# Sheet2.net
KiCad netlist of a schematic drawn in Altium Designer
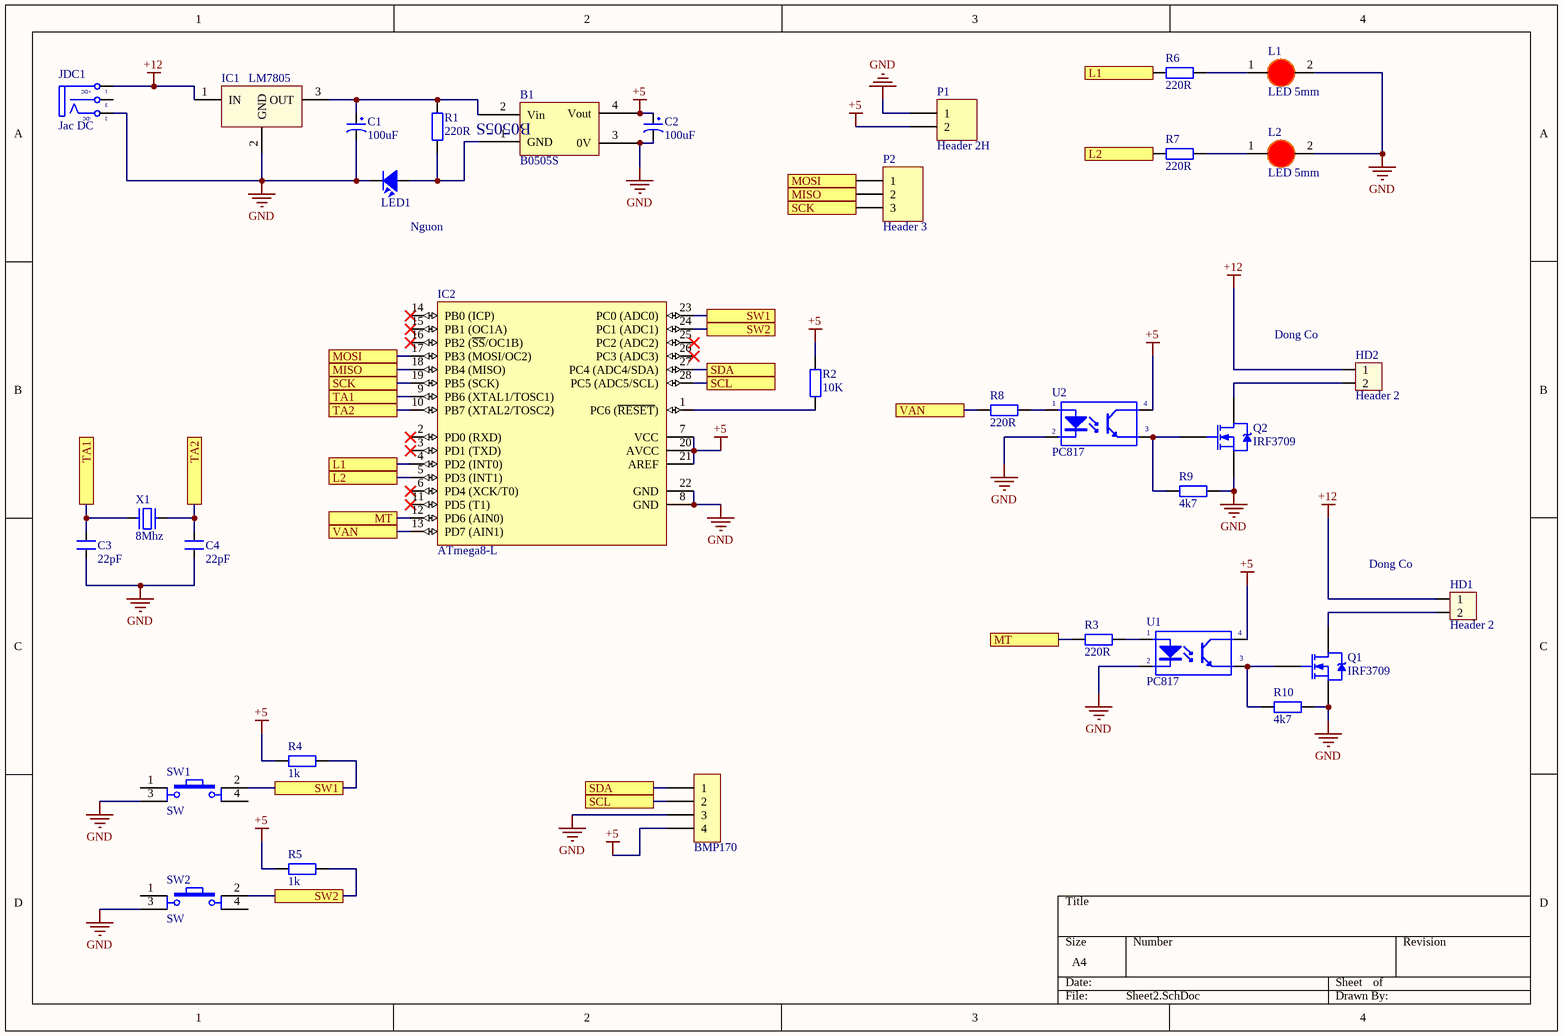
[diagram p0: Sheet2.SchDoc]

(export (version "E")
  (design (tool "Eeschema 10.0.6"))
  (components
    (comp (ref "B1")
      (value "B0505S")
      (footprint "B0505S")
      (description "Cắm")
      (libsource (lib "Altium_Lib_by_KhueNguyenCreator") (part "B0505S"))
    )
    (comp (ref "C1")
      (value "100uF")
      (footprint "tu hoa 8mm")
      (description "Cắm")
      (libsource (lib "Altium_Lib_by_KhueNguyenCreator") (part "Tu Hoa 100uF 35V 8x11"))
    )
    (comp (ref "C2")
      (value "100uF")
      (footprint "tu hoa 8mm")
      (description "Cắm")
      (libsource (lib "Altium_Lib_by_KhueNguyenCreator") (part "Tu Hoa 100uF 35V 8x11"))
    )
    (comp (ref "C3")
      (value "22pF")
      (footprint "CN1")
      (description "Cap np  1pF - 472pF")
      (libsource (lib "syhaunguyen") (part "CN1"))
    )
    (comp (ref "C4")
      (value "22pF")
      (footprint "CN1")
      (description "Cap np  1pF - 472pF")
      (libsource (lib "syhaunguyen") (part "CN1"))
    )
    (comp (ref "H1")
      (value "BMP170")
      (footprint "XH2.54M-4")
      (description "Cắm")
      (libsource (lib "Altium_Lib_by_KhueNguyenCreator") (part "Header 4P 2.54 Duc Thang"))
    )
    (comp (ref "HD1")
      (value "Header 2")
      (footprint "HED2")
      (description "Header 2 (Green)")
      (libsource (lib "syhaunguyen") (part "Hed2"))
    )
    (comp (ref "HD2")
      (value "Header 2")
      (footprint "HED2")
      (description "Header 2 (Green)")
      (libsource (lib "syhaunguyen") (part "Hed2"))
    )
    (comp (ref "IC1")
      (value "LM7805")
      (footprint "QTO-220")
      (description "On ap +, from + 5 to + 24VDC")
      (libsource (lib "syhaunguyen") (part "LM78xx"))
    )
    (comp (ref "IC2")
      (value "ATmega8-L")
      (footprint "DIP28/W0.3")
      (description "8-Bit AVR Microcontroller with 8K Bytes of In-System Programmable Flash Memory")
      (libsource (lib "syhaunguyen") (part "ATmega8-L"))
    )
    (comp (ref "JDC1")
      (value "Jac DC")
      (footprint "DC-IN")
      (description "Jac DC input")
      (libsource (lib "syhaunguyen") (part "DCIN"))
    )
    (comp (ref "L1")
      (value "LED 5mm")
      (footprint "LED-5MM-RED")
      (description "Cắm")
      (libsource (lib "Altium_Lib_by_KhueNguyenCreator") (part "LED 5mm Do"))
    )
    (comp (ref "L2")
      (value "LED 5mm")
      (footprint "LED-5MM-RED")
      (description "Cắm")
      (libsource (lib "Altium_Lib_by_KhueNguyenCreator") (part "LED 5mm Do"))
    )
    (comp (ref "LED1")
      (value "LED")
      (footprint "LED-3")
      (description "LED Single colour Green and Red")
      (libsource (lib "syhaunguyen") (part "LED"))
    )
    (comp (ref "P1")
      (value "Header 2H")
      (footprint "HDR1X2H")
      (description "Header, 2-Pin, Right Angle")
      (fields (field (name "PUBLISHER") "Altium Limited"))
      (libsource (lib "Cty1") (part "Header 2H"))
    )
    (comp (ref "P2")
      (value "Header 3")
      (footprint "HDR1X3")
      (description "Header, 3-Pin")
      (fields (field (name "PUBLISHER") "Altium Limited"))
      (libsource (lib "Cty1") (part "Header 3"))
    )
    (comp (ref "Q1")
      (value "IRF3709")
      (footprint "TO220")
      (description "N-Channel Power MOSFET")
      (libsource (lib "Altium_Lib_by_KhueNguyenCreator") (part "IRF3709 DIP"))
    )
    (comp (ref "Q2")
      (value "IRF3709")
      (footprint "TO220")
      (description "N-Channel Power MOSFET")
      (libsource (lib "Altium_Lib_by_KhueNguyenCreator") (part "IRF3709 DIP"))
    )
    (comp (ref "R1")
      (value "220R")
      (footprint "R1/4W")
      (description "Resistor 1/4W")
      (libsource (lib "syhaunguyen") (part "R1/4W"))
    )
    (comp (ref "R2")
      (value "10K")
      (footprint "R1/4W")
      (description "Resistor 1/4W")
      (libsource (lib "syhaunguyen") (part "R1/4W"))
    )
    (comp (ref "R3")
      (value "220R")
      (footprint "R1/4W")
      (description "Resistor 1/4W")
      (libsource (lib "syhaunguyen") (part "R1/4W"))
    )
    (comp (ref "R4")
      (value "1k")
      (footprint "R1/4W")
      (description "Resistor 1/4W")
      (libsource (lib "syhaunguyen") (part "R1/4W"))
    )
    (comp (ref "R5")
      (value "1k")
      (footprint "R1/4W")
      (description "Resistor 1/4W")
      (libsource (lib "syhaunguyen") (part "R1/4W"))
    )
    (comp (ref "R6")
      (value "220R")
      (footprint "R1/4W")
      (description "Resistor 1/4W")
      (libsource (lib "syhaunguyen") (part "R1/4W"))
    )
    (comp (ref "R7")
      (value "220R")
      (footprint "R1/4W")
      (description "Resistor 1/4W")
      (libsource (lib "syhaunguyen") (part "R1/4W"))
    )
    (comp (ref "R8")
      (value "220R")
      (footprint "R1/4W")
      (description "Resistor 1/4W")
      (libsource (lib "syhaunguyen") (part "R1/4W"))
    )
    (comp (ref "R9")
      (value "4k7")
      (footprint "R1/4W")
      (description "Resistor 1/4W")
      (libsource (lib "syhaunguyen") (part "R1/4W"))
    )
    (comp (ref "R10")
      (value "4k7")
      (footprint "R1/4W")
      (description "Resistor 1/4W")
      (libsource (lib "syhaunguyen") (part "R1/4W"))
    )
    (comp (ref "SW1")
      (value "SW")
      (footprint "SW4")
      (description "Switch button 4 pin")
      (libsource (lib "syhaunguyen") (part "SW4"))
    )
    (comp (ref "SW2")
      (value "SW")
      (footprint "SW4")
      (description "Switch button 4 pin")
      (libsource (lib "syhaunguyen") (part "SW4"))
    )
    (comp (ref "U1")
      (value "PC817")
      (footprint "DIP4/W0.3")
      (description "Single Opto")
      (libsource (lib "syhaunguyen") (part "PC817"))
    )
    (comp (ref "U2")
      (value "PC817")
      (footprint "DIP4/W0.3")
      (description "Single Opto")
      (libsource (lib "syhaunguyen") (part "PC817"))
    )
    (comp (ref "X1")
      (value "8Mhz")
      (footprint "XT2")
      (description "Crystal For all Crystal 2pin.")
      (libsource (lib "syhaunguyen") (part "XT2"))
    )
  )
  (nets
    (net (code "1") (name "+5") (class "Default")
      (node (ref "B1") (pin "4") (pinfunction "Vout_4") (pintype "passive"))
      (node (ref "C2") (pin "1") (pinfunction "1_1") (pintype "passive"))
      (node (ref "H1") (pin "4") (pinfunction "4_4") (pintype "passive"))
      (node (ref "IC2") (pin "20") (pinfunction "AVCC_20") (pintype "power_in"))
      (node (ref "IC2") (pin "21") (pinfunction "AREF_21") (pintype "passive"))
      (node (ref "IC2") (pin "7") (pinfunction "VCC_7") (pintype "power_in"))
      (node (ref "P1") (pin "2") (pinfunction "2_2") (pintype "passive"))
      (node (ref "R2") (pin "2") (pinfunction "2_2") (pintype "passive"))
      (node (ref "R4") (pin "2") (pinfunction "2_2") (pintype "passive"))
      (node (ref "R5") (pin "2") (pinfunction "2_2") (pintype "passive"))
      (node (ref "U1") (pin "4") (pinfunction "C_4") (pintype "passive"))
      (node (ref "U2") (pin "4") (pinfunction "C_4") (pintype "passive"))
    )
    (net (code "2") (name "+12") (class "Default")
      (node (ref "HD1") (pin "1") (pinfunction "1_1") (pintype "passive"))
      (node (ref "HD2") (pin "1") (pinfunction "1_1") (pintype "passive"))
      (node (ref "IC1") (pin "1") (pinfunction "IN_1") (pintype "passive"))
      (node (ref "JDC1") (pin "1") (pinfunction "T_1") (pintype "passive"))
    )
    (net (code "3") (name "/L1") (class "Default")
      (node (ref "IC2") (pin "4") (pinfunction "PD2_(INT0)_4") (pintype "bidirectional"))
      (node (ref "R6") (pin "1") (pinfunction "1_1") (pintype "passive"))
    )
    (net (code "4") (name "/L2") (class "Default")
      (node (ref "IC2") (pin "5") (pinfunction "PD3_(INT1)_5") (pintype "bidirectional"))
      (node (ref "R7") (pin "1") (pinfunction "1_1") (pintype "passive"))
    )
    (net (code "5") (name "/MISO") (class "Default")
      (node (ref "IC2") (pin "18") (pinfunction "PB4_(MISO)_18") (pintype "bidirectional"))
      (node (ref "P2") (pin "2") (pinfunction "2_2") (pintype "passive"))
    )
    (net (code "6") (name "/MOSI") (class "Default")
      (node (ref "IC2") (pin "17") (pinfunction "PB3_(MOSI/OC2)_17") (pintype "bidirectional"))
      (node (ref "P2") (pin "1") (pinfunction "1_1") (pintype "passive"))
    )
    (net (code "7") (name "/MT") (class "Default")
      (node (ref "IC2") (pin "12") (pinfunction "PD6_(AIN0)_12") (pintype "bidirectional"))
      (node (ref "R3") (pin "1") (pinfunction "1_1") (pintype "passive"))
    )
    (net (code "8") (name "/SCK") (class "Default")
      (node (ref "IC2") (pin "19") (pinfunction "PB5_(SCK)_19") (pintype "bidirectional"))
      (node (ref "P2") (pin "3") (pinfunction "3_3") (pintype "passive"))
    )
    (net (code "9") (name "/SCL") (class "Default")
      (node (ref "H1") (pin "2") (pinfunction "2_2") (pintype "passive"))
      (node (ref "IC2") (pin "28") (pinfunction "PC5_(ADC5/SCL)_28") (pintype "bidirectional"))
    )
    (net (code "10") (name "/SDA") (class "Default")
      (node (ref "H1") (pin "1") (pinfunction "1_1") (pintype "passive"))
      (node (ref "IC2") (pin "27") (pinfunction "PC4_(ADC4/SDA)_27") (pintype "bidirectional"))
    )
    (net (code "11") (name "/SW1") (class "Default")
      (node (ref "IC2") (pin "23") (pinfunction "PC0_(ADC0)_23") (pintype "bidirectional"))
      (node (ref "R4") (pin "1") (pinfunction "1_1") (pintype "passive"))
      (node (ref "SW1") (pin "2") (pintype "passive"))
    )
    (net (code "12") (name "/SW2") (class "Default")
      (node (ref "IC2") (pin "24") (pinfunction "PC1_(ADC1)_24") (pintype "bidirectional"))
      (node (ref "R5") (pin "1") (pinfunction "1_1") (pintype "passive"))
      (node (ref "SW2") (pin "2") (pintype "passive"))
    )
    (net (code "13") (name "/TA1") (class "Default")
      (node (ref "C3") (pin "2") (pinfunction "2_2") (pintype "passive"))
      (node (ref "IC2") (pin "9") (pinfunction "PB6_(XTAL1/TOSC1)_9") (pintype "bidirectional"))
      (node (ref "X1") (pin "1") (pinfunction "1_1") (pintype "passive"))
    )
    (net (code "14") (name "/TA2") (class "Default")
      (node (ref "C4") (pin "2") (pinfunction "2_2") (pintype "passive"))
      (node (ref "IC2") (pin "10") (pinfunction "PB7_(XTAL2/TOSC2)_10") (pintype "bidirectional"))
      (node (ref "X1") (pin "2") (pinfunction "2_2") (pintype "passive"))
    )
    (net (code "15") (name "/VAN") (class "Default")
      (node (ref "IC2") (pin "13") (pinfunction "PD7_(AIN1)_13") (pintype "bidirectional"))
      (node (ref "R8") (pin "1") (pinfunction "1_1") (pintype "passive"))
    )
    (net (code "16") (name "GND") (class "Default")
      (node (ref "B1") (pin "3") (pinfunction "0V_3") (pintype "passive"))
      (node (ref "C1") (pin "2") (pinfunction "2_2") (pintype "passive"))
      (node (ref "C2") (pin "2") (pinfunction "2_2") (pintype "passive"))
      (node (ref "C3") (pin "1") (pinfunction "1_1") (pintype "passive"))
      (node (ref "C4") (pin "1") (pinfunction "1_1") (pintype "passive"))
      (node (ref "H1") (pin "3") (pinfunction "3_3") (pintype "passive"))
      (node (ref "IC1") (pin "2") (pinfunction "GND_2") (pintype "passive"))
      (node (ref "IC2") (pin "22") (pinfunction "GND_22") (pintype "power_in"))
      (node (ref "IC2") (pin "8") (pinfunction "GND_8") (pintype "power_in"))
      (node (ref "JDC1") (pin "2") (pinfunction "TN_2") (pintype "passive"))
      (node (ref "L1") (pin "2") (pinfunction "K_2") (pintype "passive"))
      (node (ref "L2") (pin "2") (pinfunction "K_2") (pintype "passive"))
      (node (ref "LED1") (pin "2") (pinfunction "2_2") (pintype "passive"))
      (node (ref "P1") (pin "1") (pinfunction "1_1") (pintype "passive"))
      (node (ref "Q1") (pin "3") (pinfunction "S_3") (pintype "passive"))
      (node (ref "Q2") (pin "3") (pinfunction "S_3") (pintype "passive"))
      (node (ref "R10") (pin "2") (pinfunction "2_2") (pintype "passive"))
      (node (ref "R9") (pin "2") (pinfunction "2_2") (pintype "passive"))
      (node (ref "SW1") (pin "3") (pintype "passive"))
      (node (ref "SW2") (pin "3") (pintype "passive"))
      (node (ref "U1") (pin "2") (pinfunction "K_2") (pintype "passive"))
      (node (ref "U2") (pin "2") (pinfunction "K_2") (pintype "passive"))
    )
    (net (code "17") (name "Net-(B1-GND)") (class "Default")
      (node (ref "B1") (pin "1") (pinfunction "GND_1") (pintype "passive"))
      (node (ref "LED1") (pin "1") (pinfunction "1_1") (pintype "passive"))
      (node (ref "R1") (pin "2") (pinfunction "2_2") (pintype "passive"))
    )
    (net (code "18") (name "Net-(B1-Vin)") (class "Default")
      (node (ref "B1") (pin "2") (pinfunction "Vin_2") (pintype "passive"))
      (node (ref "C1") (pin "1") (pinfunction "1_1") (pintype "passive"))
      (node (ref "IC1") (pin "3") (pinfunction "OUT_3") (pintype "passive"))
      (node (ref "R1") (pin "1") (pinfunction "1_1") (pintype "passive"))
    )
    (net (code "19") (name "Net-(IC2-PC6_(~{RESET}))") (class "Default")
      (node (ref "IC2") (pin "1") (pinfunction "PC6_(~{RESET})_1") (pintype "bidirectional"))
      (node (ref "R2") (pin "1") (pinfunction "1_1") (pintype "passive"))
    )
    (net (code "20") (name "Net-(L1-A)") (class "Default")
      (node (ref "L1") (pin "1") (pinfunction "A_1") (pintype "passive"))
      (node (ref "R6") (pin "2") (pinfunction "2_2") (pintype "passive"))
    )
    (net (code "21") (name "Net-(L2-A)") (class "Default")
      (node (ref "L2") (pin "1") (pinfunction "A_1") (pintype "passive"))
      (node (ref "R7") (pin "2") (pinfunction "2_2") (pintype "passive"))
    )
    (net (code "22") (name "Net-(Q1-D)") (class "Default")
      (node (ref "HD1") (pin "2") (pinfunction "2_2") (pintype "passive"))
      (node (ref "Q1") (pin "2") (pinfunction "D_2") (pintype "passive"))
    )
    (net (code "23") (name "Net-(Q1-G)") (class "Default")
      (node (ref "Q1") (pin "1") (pinfunction "G_1") (pintype "passive"))
      (node (ref "R10") (pin "1") (pinfunction "1_1") (pintype "passive"))
      (node (ref "U1") (pin "3") (pinfunction "E_3") (pintype "passive"))
    )
    (net (code "24") (name "Net-(Q2-D)") (class "Default")
      (node (ref "HD2") (pin "2") (pinfunction "2_2") (pintype "passive"))
      (node (ref "Q2") (pin "2") (pinfunction "D_2") (pintype "passive"))
    )
    (net (code "25") (name "Net-(Q2-G)") (class "Default")
      (node (ref "Q2") (pin "1") (pinfunction "G_1") (pintype "passive"))
      (node (ref "R9") (pin "1") (pinfunction "1_1") (pintype "passive"))
      (node (ref "U2") (pin "3") (pinfunction "E_3") (pintype "passive"))
    )
    (net (code "26") (name "Net-(U1-A)") (class "Default")
      (node (ref "R3") (pin "2") (pinfunction "2_2") (pintype "passive"))
      (node (ref "U1") (pin "1") (pinfunction "A_1") (pintype "passive"))
    )
    (net (code "27") (name "Net-(U2-A)") (class "Default")
      (node (ref "R8") (pin "2") (pinfunction "2_2") (pintype "passive"))
      (node (ref "U2") (pin "1") (pinfunction "A_1") (pintype "passive"))
    )
    (net (code "28") (name "unconnected-(IC2-PB0_(ICP)-Pad14)") (class "Default")
      (node (ref "IC2") (pin "14") (pinfunction "PB0_(ICP)_14") (pintype "bidirectional+no_connect"))
    )
    (net (code "29") (name "unconnected-(IC2-PB1_(OC1A)-Pad15)") (class "Default")
      (node (ref "IC2") (pin "15") (pinfunction "PB1_(OC1A)_15") (pintype "bidirectional+no_connect"))
    )
    (net (code "30") (name "unconnected-(IC2-PB2_(~{SS}{slash}OC1B)-Pad16)") (class "Default")
      (node (ref "IC2") (pin "16") (pinfunction "PB2_(~{SS}/OC1B)_16") (pintype "bidirectional+no_connect"))
    )
    (net (code "31") (name "unconnected-(IC2-PC2_(ADC2)-Pad25)") (class "Default")
      (node (ref "IC2") (pin "25") (pinfunction "PC2_(ADC2)_25") (pintype "bidirectional+no_connect"))
    )
    (net (code "32") (name "unconnected-(IC2-PC3_(ADC3)-Pad26)") (class "Default")
      (node (ref "IC2") (pin "26") (pinfunction "PC3_(ADC3)_26") (pintype "bidirectional+no_connect"))
    )
    (net (code "33") (name "unconnected-(IC2-PD0_(RXD)-Pad2)") (class "Default")
      (node (ref "IC2") (pin "2") (pinfunction "PD0_(RXD)_2") (pintype "bidirectional+no_connect"))
    )
    (net (code "34") (name "unconnected-(IC2-PD1_(TXD)-Pad3)") (class "Default")
      (node (ref "IC2") (pin "3") (pinfunction "PD1_(TXD)_3") (pintype "bidirectional+no_connect"))
    )
    (net (code "35") (name "unconnected-(IC2-PD4_(XCK{slash}T0)-Pad6)") (class "Default")
      (node (ref "IC2") (pin "6") (pinfunction "PD4_(XCK/T0)_6") (pintype "bidirectional+no_connect"))
    )
    (net (code "36") (name "unconnected-(IC2-PD5_(T1)-Pad11)") (class "Default")
      (node (ref "IC2") (pin "11") (pinfunction "PD5_(T1)_11") (pintype "bidirectional+no_connect"))
    )
    (net (code "37") (name "unconnected-(JDC1-S-Pad3)") (class "Default")
      (node (ref "JDC1") (pin "3") (pinfunction "S_3") (pintype "power_in"))
    )
    (net (code "38") (name "unconnected-(SW1-Pad1)") (class "Default")
      (node (ref "SW1") (pin "1") (pintype "passive"))
    )
    (net (code "39") (name "unconnected-(SW1-Pad4)") (class "Default")
      (node (ref "SW1") (pin "4") (pintype "passive"))
    )
    (net (code "40") (name "unconnected-(SW2-Pad1)") (class "Default")
      (node (ref "SW2") (pin "1") (pintype "passive"))
    )
    (net (code "41") (name "unconnected-(SW2-Pad4)") (class "Default")
      (node (ref "SW2") (pin "4") (pintype "passive"))
    )
  )
)
